# rony_4_hall_sensor.net
KiCad netlist of a schematic drawn in EAGLE
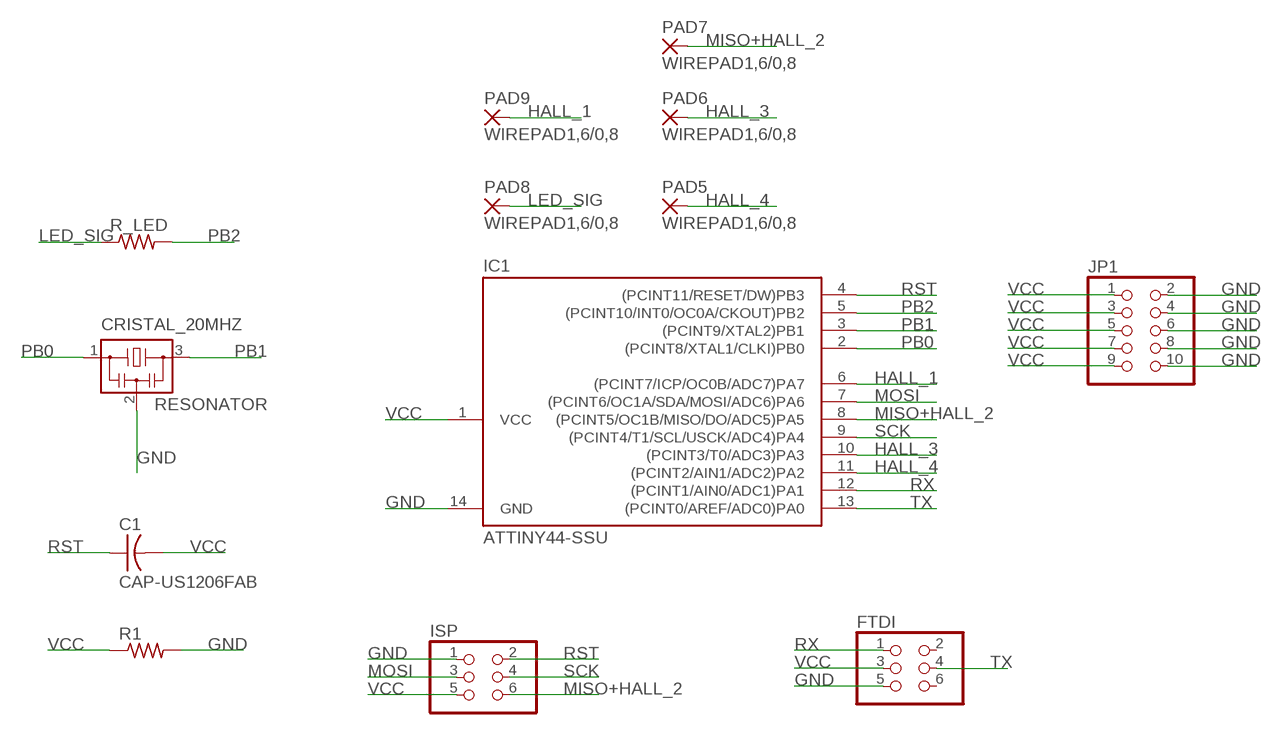
[diagram p0: schematic, sheet 1]

(export (version "E")
  (design (tool "Eeschema 10.0.6"))
  (components
    (comp (ref "C1")
      (value "CAP-US1206FAB")
      (footprint "eagle-import:C1206FAB")
      (libsource (lib "eagle-import") (part "CAP-US1206FAB"))
    )
    (comp (ref "CRISTAL_20MHZ")
      (value "RESONATOR")
      (footprint "eagle-import:EFOBM")
      (libsource (lib "eagle-import") (part "RESONATOR"))
    )
    (comp (ref "FTDI")
      (value "PINHD-2X3-SMD")
      (footprint "eagle-import:2X03SMD")
      (libsource (lib "eagle-import") (part "PINHD-2X3-SMD"))
    )
    (comp (ref "IC1")
      (value "ATTINY44-SSU")
      (footprint "eagle-import:SOIC14")
      (libsource (lib "eagle-import") (part "ATTINY44-SSU"))
    )
    (comp (ref "ISP")
      (value "PINHD-2X3-SMD")
      (footprint "eagle-import:2X03SMD")
      (libsource (lib "eagle-import") (part "PINHD-2X3-SMD"))
    )
    (comp (ref "JP1")
      (value "PINHD-2X5")
      (footprint "eagle-import:2X05")
      (libsource (lib "eagle-import") (part "PINHD-2X5"))
    )
    (comp (ref "PAD5")
      (value "WIREPAD1,6/0,8")
      (footprint "eagle-import:1,6_0,8")
      (libsource (lib "eagle-import") (part "WIREPAD1,6/0,8"))
    )
    (comp (ref "PAD6")
      (value "WIREPAD1,6/0,8")
      (footprint "eagle-import:1,6_0,8")
      (libsource (lib "eagle-import") (part "WIREPAD1,6/0,8"))
    )
    (comp (ref "PAD7")
      (value "WIREPAD1,6/0,8")
      (footprint "eagle-import:1,6_0,8")
      (libsource (lib "eagle-import") (part "WIREPAD1,6/0,8"))
    )
    (comp (ref "PAD8")
      (value "WIREPAD1,6/0,8")
      (footprint "eagle-import:1,6_0,8")
      (libsource (lib "eagle-import") (part "WIREPAD1,6/0,8"))
    )
    (comp (ref "PAD9")
      (value "WIREPAD1,6/0,8")
      (footprint "eagle-import:1,6_0,8")
      (libsource (lib "eagle-import") (part "WIREPAD1,6/0,8"))
    )
    (comp (ref "R1")
      (value "RES-US1206FAB")
      (footprint "eagle-import:R1206FAB")
      (libsource (lib "eagle-import") (part "RES-US1206FAB"))
    )
    (comp (ref "R_LED")
      (value "RES-US1206FAB")
      (footprint "eagle-import:R1206FAB")
      (libsource (lib "eagle-import") (part "RES-US1206FAB"))
    )
  )
  (nets
    (net (code "1") (name "/GND") (class "Default")
      (node (ref "CRISTAL_20MHZ") (pin "2") (pinfunction "2_2") (pintype "passive"))
      (node (ref "FTDI") (pin "5") (pinfunction "5_5") (pintype "passive"))
      (node (ref "IC1") (pin "14") (pinfunction "GND_14") (pintype "power_in"))
      (node (ref "ISP") (pin "1") (pinfunction "1_1") (pintype "passive"))
      (node (ref "JP1") (pin "10") (pinfunction "10_10") (pintype "passive"))
      (node (ref "JP1") (pin "2") (pinfunction "2_2") (pintype "passive"))
      (node (ref "JP1") (pin "4") (pinfunction "4_4") (pintype "passive"))
      (node (ref "JP1") (pin "6") (pinfunction "6_6") (pintype "passive"))
      (node (ref "JP1") (pin "8") (pinfunction "8_8") (pintype "passive"))
      (node (ref "R1") (pin "2") (pinfunction "2_2") (pintype "passive"))
    )
    (net (code "2") (name "/HALL_1") (class "Default")
      (node (ref "IC1") (pin "6") (pinfunction "(PCINT7/ICP/OC0B/ADC7)PA7_6") (pintype "bidirectional"))
      (node (ref "PAD9") (pin "1") (pinfunction "P_1") (pintype "passive"))
    )
    (net (code "3") (name "/HALL_3") (class "Default")
      (node (ref "IC1") (pin "10") (pinfunction "(PCINT3/T0/ADC3)PA3_10") (pintype "bidirectional"))
      (node (ref "PAD6") (pin "1") (pinfunction "P_1") (pintype "passive"))
    )
    (net (code "4") (name "/HALL_4") (class "Default")
      (node (ref "IC1") (pin "11") (pinfunction "(PCINT2/AIN1/ADC2)PA2_11") (pintype "bidirectional"))
      (node (ref "PAD5") (pin "1") (pinfunction "P_1") (pintype "passive"))
    )
    (net (code "5") (name "/LED_SIG") (class "Default")
      (node (ref "PAD8") (pin "1") (pinfunction "P_1") (pintype "passive"))
      (node (ref "R_LED") (pin "1") (pinfunction "1_1") (pintype "passive"))
    )
    (net (code "6") (name "/MISO+HALL_2") (class "Default")
      (node (ref "IC1") (pin "8") (pinfunction "(PCINT5/OC1B/MISO/DO/ADC5)PA5_8") (pintype "bidirectional"))
      (node (ref "ISP") (pin "6") (pinfunction "6_6") (pintype "passive"))
      (node (ref "PAD7") (pin "1") (pinfunction "P_1") (pintype "passive"))
    )
    (net (code "7") (name "/MOSI") (class "Default")
      (node (ref "IC1") (pin "7") (pinfunction "(PCINT6/OC1A/SDA/MOSI/ADC6)PA6_7") (pintype "bidirectional"))
      (node (ref "ISP") (pin "3") (pinfunction "3_3") (pintype "passive"))
    )
    (net (code "8") (name "/PB0") (class "Default")
      (node (ref "CRISTAL_20MHZ") (pin "1") (pinfunction "1_1") (pintype "passive"))
      (node (ref "IC1") (pin "2") (pinfunction "(PCINT8/XTAL1/CLKI)PB0_2") (pintype "bidirectional"))
    )
    (net (code "9") (name "/PB1") (class "Default")
      (node (ref "CRISTAL_20MHZ") (pin "3") (pinfunction "3_3") (pintype "passive"))
      (node (ref "IC1") (pin "3") (pinfunction "(PCINT9/XTAL2)PB1_3") (pintype "bidirectional"))
    )
    (net (code "10") (name "/PB2") (class "Default")
      (node (ref "IC1") (pin "5") (pinfunction "(PCINT10/INT0/OC0A/CKOUT)PB2_5") (pintype "bidirectional"))
      (node (ref "R_LED") (pin "2") (pinfunction "2_2") (pintype "passive"))
    )
    (net (code "11") (name "/RST") (class "Default")
      (node (ref "C1") (pin "1") (pinfunction "1_1") (pintype "passive"))
      (node (ref "IC1") (pin "4") (pinfunction "(PCINT11/RESET/DW)PB3_4") (pintype "bidirectional"))
      (node (ref "ISP") (pin "2") (pinfunction "2_2") (pintype "passive"))
    )
    (net (code "12") (name "/RX") (class "Default")
      (node (ref "FTDI") (pin "1") (pinfunction "1_1") (pintype "passive"))
      (node (ref "IC1") (pin "12") (pinfunction "(PCINT1/AIN0/ADC1)PA1_12") (pintype "bidirectional"))
    )
    (net (code "13") (name "/SCK") (class "Default")
      (node (ref "IC1") (pin "9") (pinfunction "(PCINT4/T1/SCL/USCK/ADC4)PA4_9") (pintype "bidirectional"))
      (node (ref "ISP") (pin "4") (pinfunction "4_4") (pintype "passive"))
    )
    (net (code "14") (name "/TX") (class "Default")
      (node (ref "FTDI") (pin "4") (pinfunction "4_4") (pintype "passive"))
      (node (ref "IC1") (pin "13") (pinfunction "(PCINT0/AREF/ADC0)PA0_13") (pintype "bidirectional"))
    )
    (net (code "15") (name "/VCC") (class "Default")
      (node (ref "C1") (pin "2") (pinfunction "2_2") (pintype "passive"))
      (node (ref "FTDI") (pin "3") (pinfunction "3_3") (pintype "passive"))
      (node (ref "IC1") (pin "1") (pinfunction "VCC_1") (pintype "power_in"))
      (node (ref "ISP") (pin "5") (pinfunction "5_5") (pintype "passive"))
      (node (ref "JP1") (pin "1") (pinfunction "1_1") (pintype "passive"))
      (node (ref "JP1") (pin "3") (pinfunction "3_3") (pintype "passive"))
      (node (ref "JP1") (pin "5") (pinfunction "5_5") (pintype "passive"))
      (node (ref "JP1") (pin "7") (pinfunction "7_7") (pintype "passive"))
      (node (ref "JP1") (pin "9") (pinfunction "9_9") (pintype "passive"))
      (node (ref "R1") (pin "1") (pinfunction "1_1") (pintype "passive"))
    )
    (net (code "16") (name "unconnected-(FTDI-Pad2)") (class "Default")
      (node (ref "FTDI") (pin "2") (pinfunction "2_2") (pintype "passive"))
    )
    (net (code "17") (name "unconnected-(FTDI-Pad6)") (class "Default")
      (node (ref "FTDI") (pin "6") (pinfunction "6_6") (pintype "passive"))
    )
  )
)
